# LCD.net
KiCad netlist of a schematic drawn in Altium Designer
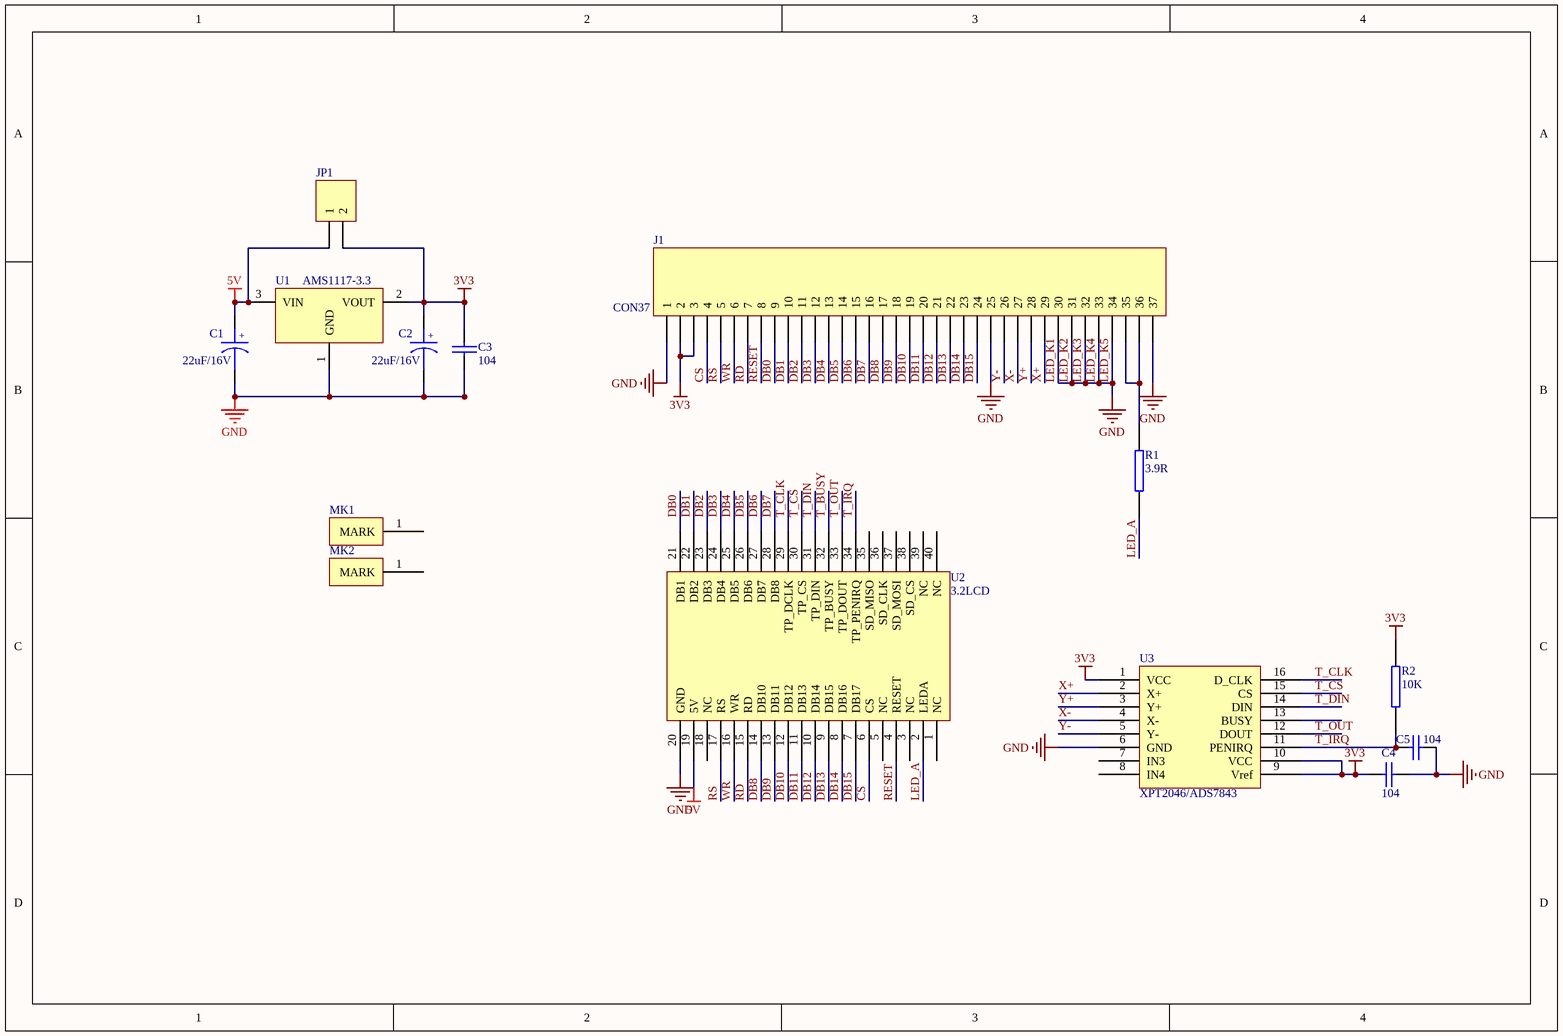
[diagram p0: LCD.SchDoc]

(export (version "E")
  (design (tool "Eeschema 10.0.6"))
  (components
    (comp (ref "C1")
      (value "22uF/16V")
      (footprint "0805C")
      (description "Capacitor")
      (libsource (lib "*") (part "CAPACITOR POL"))
    )
    (comp (ref "C2")
      (value "22uF/16V")
      (footprint "0805C")
      (description "Capacitor")
      (libsource (lib "*") (part "CAPACITOR POL"))
    )
    (comp (ref "C3")
      (value "104")
      (footprint "C0603")
      (description "Capacitor")
      (libsource (lib "*") (part "CAP"))
    )
    (comp (ref "C4")
      (value "104")
      (footprint "C0603")
      (description "Capacitor")
      (libsource (lib "*") (part "CAP"))
    )
    (comp (ref "C5")
      (value "104")
      (footprint "C0603")
      (description "Capacitor")
      (libsource (lib "*") (part "CAP"))
    )
    (comp (ref "J1")
      (value "CON37")
      (footprint "3.2_37PIN_ILI9341B")
      (description "Header, 6-Pin")
      (fields (field (name "PUBLISHER") "Altium Limited"))
      (libsource (lib "mediaV3.0") (part "Header 37"))
    )
    (comp (ref "JP1")
      (value "~")
      (footprint "J")
      (description "Header, 2-Pin")
      (fields (field (name "PUBLISHER") "Altium Limited"))
      (libsource (lib "Miscellaneous Connectors") (part "Header 2"))
    )
    (comp (ref "MK1") (value "~") (footprint "MARK") (libsource (lib "kevin") (part "MARK")))
    (comp (ref "MK2") (value "~") (footprint "MARK") (libsource (lib "kevin") (part "MARK")))
    (comp (ref "R1") (value "3.9R") (footprint "R0603") (libsource (lib "*") (part "RES2")))
    (comp (ref "R2") (value "10K") (footprint "R0603") (libsource (lib "*") (part "RES2")))
    (comp (ref "U1") (value "AMS1117-3.3") (footprint "SOT-223/P2.3") (libsource (lib "*") (part "AMS1117")))
    (comp (ref "U2") (value "3.2LCD") (footprint "LCD-DIP") (libsource (lib "media") (part "3.2LCD")))
    (comp (ref "U3")
      (value "XPT2046/ADS7843")
      (footprint "TSSOP-16")
      (libsource (lib "mediaV3.0") (part "XPT2046"))
    )
  )
  (nets
    (net (code "1") (name "/CS") (class "Default")
      (node (ref "J1") (pin "4") (pinfunction "4_4") (pintype "passive"))
      (node (ref "U2") (pin "6") (pinfunction "CS_6") (pintype "passive"))
    )
    (net (code "2") (name "/DB0") (class "Default")
      (node (ref "J1") (pin "9") (pinfunction "9_9") (pintype "passive"))
      (node (ref "U2") (pin "21") (pinfunction "DB1_21") (pintype "passive"))
    )
    (net (code "3") (name "/DB1") (class "Default")
      (node (ref "J1") (pin "10") (pinfunction "10_10") (pintype "passive"))
      (node (ref "U2") (pin "22") (pinfunction "DB2_22") (pintype "passive"))
    )
    (net (code "4") (name "/DB2") (class "Default")
      (node (ref "J1") (pin "11") (pinfunction "11_11") (pintype "passive"))
      (node (ref "U2") (pin "23") (pinfunction "DB3_23") (pintype "passive"))
    )
    (net (code "5") (name "/DB3") (class "Default")
      (node (ref "J1") (pin "12") (pinfunction "12_12") (pintype "passive"))
      (node (ref "U2") (pin "24") (pinfunction "DB4_24") (pintype "passive"))
    )
    (net (code "6") (name "/DB4") (class "Default")
      (node (ref "J1") (pin "13") (pinfunction "13_13") (pintype "passive"))
      (node (ref "U2") (pin "25") (pinfunction "DB5_25") (pintype "passive"))
    )
    (net (code "7") (name "/DB5") (class "Default")
      (node (ref "J1") (pin "14") (pinfunction "14_14") (pintype "passive"))
      (node (ref "U2") (pin "26") (pinfunction "DB6_26") (pintype "passive"))
    )
    (net (code "8") (name "/DB6") (class "Default")
      (node (ref "J1") (pin "15") (pinfunction "15_15") (pintype "passive"))
      (node (ref "U2") (pin "27") (pinfunction "DB7_27") (pintype "passive"))
    )
    (net (code "9") (name "/DB7") (class "Default")
      (node (ref "J1") (pin "16") (pinfunction "16_16") (pintype "passive"))
      (node (ref "U2") (pin "28") (pinfunction "DB8_28") (pintype "passive"))
    )
    (net (code "10") (name "/DB8") (class "Default")
      (node (ref "J1") (pin "17") (pinfunction "17_17") (pintype "passive"))
      (node (ref "U2") (pin "14") (pinfunction "DB10_14") (pintype "passive"))
    )
    (net (code "11") (name "/DB9") (class "Default")
      (node (ref "J1") (pin "18") (pinfunction "18_18") (pintype "passive"))
      (node (ref "U2") (pin "13") (pinfunction "DB11_13") (pintype "passive"))
    )
    (net (code "12") (name "/DB10") (class "Default")
      (node (ref "J1") (pin "19") (pinfunction "19_19") (pintype "passive"))
      (node (ref "U2") (pin "12") (pinfunction "DB12_12") (pintype "passive"))
    )
    (net (code "13") (name "/DB11") (class "Default")
      (node (ref "J1") (pin "20") (pinfunction "20_20") (pintype "passive"))
      (node (ref "U2") (pin "11") (pinfunction "DB13_11") (pintype "passive"))
    )
    (net (code "14") (name "/DB12") (class "Default")
      (node (ref "J1") (pin "21") (pinfunction "21_21") (pintype "passive"))
      (node (ref "U2") (pin "10") (pinfunction "DB14_10") (pintype "passive"))
    )
    (net (code "15") (name "/DB13") (class "Default")
      (node (ref "J1") (pin "22") (pinfunction "22_22") (pintype "passive"))
      (node (ref "U2") (pin "9") (pinfunction "DB15_9") (pintype "passive"))
    )
    (net (code "16") (name "/DB14") (class "Default")
      (node (ref "J1") (pin "23") (pinfunction "23_23") (pintype "passive"))
      (node (ref "U2") (pin "8") (pinfunction "DB16_8") (pintype "passive"))
    )
    (net (code "17") (name "/DB15") (class "Default")
      (node (ref "J1") (pin "24") (pinfunction "24_24") (pintype "passive"))
      (node (ref "U2") (pin "7") (pinfunction "DB17_7") (pintype "passive"))
    )
    (net (code "18") (name "/LED_A") (class "Default")
      (node (ref "R1") (pin "1") (pinfunction "1_1") (pintype "passive"))
      (node (ref "U2") (pin "2") (pinfunction "LEDA_2") (pintype "passive"))
    )
    (net (code "19") (name "/RD") (class "Default")
      (node (ref "J1") (pin "7") (pinfunction "7_7") (pintype "passive"))
      (node (ref "U2") (pin "15") (pinfunction "RD_15") (pintype "passive"))
    )
    (net (code "20") (name "/RESET") (class "Default")
      (node (ref "J1") (pin "8") (pinfunction "8_8") (pintype "passive"))
      (node (ref "U2") (pin "4") (pinfunction "RESET_4") (pintype "passive"))
    )
    (net (code "21") (name "/RS") (class "Default")
      (node (ref "J1") (pin "5") (pinfunction "5_5") (pintype "passive"))
      (node (ref "U2") (pin "17") (pinfunction "RS_17") (pintype "passive"))
    )
    (net (code "22") (name "/T_BUSY") (class "Default")
      (node (ref "U2") (pin "32") (pinfunction "TP_BUSY_32") (pintype "passive"))
    )
    (net (code "23") (name "/T_CLK") (class "Default")
      (node (ref "U2") (pin "29") (pinfunction "TP_DCLK_29") (pintype "passive"))
      (node (ref "U3") (pin "16") (pinfunction "D_CLK_16") (pintype "passive"))
    )
    (net (code "24") (name "/T_CS") (class "Default")
      (node (ref "U2") (pin "30") (pinfunction "TP_CS_30") (pintype "passive"))
      (node (ref "U3") (pin "15") (pinfunction "CS_15") (pintype "passive"))
    )
    (net (code "25") (name "/T_DIN") (class "Default")
      (node (ref "U2") (pin "31") (pinfunction "TP_DIN_31") (pintype "passive"))
      (node (ref "U3") (pin "14") (pinfunction "DIN_14") (pintype "passive"))
    )
    (net (code "26") (name "/T_IRQ") (class "Default")
      (node (ref "C5") (pin "1") (pinfunction "1_1") (pintype "passive"))
      (node (ref "R2") (pin "2") (pinfunction "2_2") (pintype "passive"))
      (node (ref "U2") (pin "34") (pinfunction "TP_PENIRQ_34") (pintype "passive"))
      (node (ref "U3") (pin "11") (pinfunction "PENIRQ_11") (pintype "passive"))
    )
    (net (code "27") (name "/T_OUT") (class "Default")
      (node (ref "U2") (pin "33") (pinfunction "TP_DOUT_33") (pintype "passive"))
      (node (ref "U3") (pin "12") (pinfunction "DOUT_12") (pintype "passive"))
    )
    (net (code "28") (name "/WR") (class "Default")
      (node (ref "J1") (pin "6") (pinfunction "6_6") (pintype "passive"))
      (node (ref "U2") (pin "16") (pinfunction "WR_16") (pintype "passive"))
    )
    (net (code "29") (name "/X+") (class "Default")
      (node (ref "J1") (pin "29") (pinfunction "29_29") (pintype "passive"))
      (node (ref "U3") (pin "2") (pinfunction "X+_2") (pintype "passive"))
    )
    (net (code "30") (name "/X-") (class "Default")
      (node (ref "J1") (pin "27") (pinfunction "27_27") (pintype "passive"))
      (node (ref "U3") (pin "4") (pinfunction "X-_4") (pintype "passive"))
    )
    (net (code "31") (name "/Y+") (class "Default")
      (node (ref "J1") (pin "28") (pinfunction "28_28") (pintype "passive"))
      (node (ref "U3") (pin "3") (pinfunction "Y+_3") (pintype "passive"))
    )
    (net (code "32") (name "/Y-") (class "Default")
      (node (ref "J1") (pin "26") (pinfunction "26_26") (pintype "passive"))
      (node (ref "U3") (pin "5") (pinfunction "Y-_5") (pintype "passive"))
    )
    (net (code "33") (name "3V3") (class "Default")
      (node (ref "C2") (pin "1") (pinfunction "1_1") (pintype "passive"))
      (node (ref "C3") (pin "1") (pinfunction "1_1") (pintype "passive"))
      (node (ref "C4") (pin "1") (pinfunction "1_1") (pintype "passive"))
      (node (ref "J1") (pin "2") (pinfunction "2_2") (pintype "passive"))
      (node (ref "J1") (pin "3") (pinfunction "3_3") (pintype "passive"))
      (node (ref "JP1") (pin "2") (pinfunction "2_2") (pintype "passive"))
      (node (ref "R2") (pin "1") (pinfunction "1_1") (pintype "passive"))
      (node (ref "U1") (pin "2") (pinfunction "VOUT_2") (pintype "passive"))
      (node (ref "U3") (pin "1") (pinfunction "VCC_1") (pintype "passive"))
      (node (ref "U3") (pin "10") (pinfunction "VCC_10") (pintype "passive"))
      (node (ref "U3") (pin "9") (pinfunction "Vref_9") (pintype "passive"))
    )
    (net (code "34") (name "5V") (class "Default")
      (node (ref "C1") (pin "1") (pinfunction "1_1") (pintype "passive"))
      (node (ref "JP1") (pin "1") (pinfunction "1_1") (pintype "passive"))
      (node (ref "U1") (pin "3") (pinfunction "VIN_3") (pintype "passive"))
      (node (ref "U2") (pin "19") (pinfunction "5V_19") (pintype "passive"))
    )
    (net (code "35") (name "GND") (class "Default")
      (node (ref "C1") (pin "2") (pinfunction "2_2") (pintype "passive"))
      (node (ref "C2") (pin "2") (pinfunction "2_2") (pintype "passive"))
      (node (ref "C3") (pin "2") (pinfunction "2_2") (pintype "passive"))
      (node (ref "C4") (pin "2") (pinfunction "2_2") (pintype "passive"))
      (node (ref "C5") (pin "2") (pinfunction "2_2") (pintype "passive"))
      (node (ref "J1") (pin "1") (pinfunction "1_1") (pintype "passive"))
      (node (ref "J1") (pin "25") (pinfunction "25_25") (pintype "passive"))
      (node (ref "J1") (pin "30") (pinfunction "30_30") (pintype "passive"))
      (node (ref "J1") (pin "31") (pinfunction "31_31") (pintype "passive"))
      (node (ref "J1") (pin "32") (pinfunction "32_32") (pintype "passive"))
      (node (ref "J1") (pin "33") (pinfunction "33_33") (pintype "passive"))
      (node (ref "J1") (pin "34") (pinfunction "34_34") (pintype "passive"))
      (node (ref "J1") (pin "37") (pinfunction "37_37") (pintype "passive"))
      (node (ref "U1") (pin "1") (pinfunction "GND_1") (pintype "passive"))
      (node (ref "U2") (pin "20") (pinfunction "GND_20") (pintype "passive"))
      (node (ref "U3") (pin "6") (pinfunction "GND_6") (pintype "passive"))
    )
    (net (code "36") (name "Net-(J1-Pad35)") (class "Default")
      (node (ref "J1") (pin "35") (pinfunction "35_35") (pintype "passive"))
      (node (ref "J1") (pin "36") (pinfunction "36_36") (pintype "passive"))
      (node (ref "R1") (pin "2") (pinfunction "2_2") (pintype "passive"))
    )
    (net (code "37") (name "unconnected-(MK1-MARK-Pad1)") (class "Default")
      (node (ref "MK1") (pin "1") (pinfunction "MARK_1") (pintype "passive"))
    )
    (net (code "38") (name "unconnected-(MK2-MARK-Pad1)") (class "Default")
      (node (ref "MK2") (pin "1") (pinfunction "MARK_1") (pintype "passive"))
    )
    (net (code "39") (name "unconnected-(U2-NC-Pad1)") (class "Default")
      (node (ref "U2") (pin "1") (pinfunction "NC_1") (pintype "passive"))
    )
    (net (code "40") (name "unconnected-(U2-NC-Pad3)") (class "Default")
      (node (ref "U2") (pin "3") (pinfunction "NC_3") (pintype "passive"))
    )
    (net (code "41") (name "unconnected-(U2-NC-Pad5)") (class "Default")
      (node (ref "U2") (pin "5") (pinfunction "NC_5") (pintype "passive"))
    )
    (net (code "42") (name "unconnected-(U2-NC-Pad18)") (class "Default")
      (node (ref "U2") (pin "18") (pinfunction "NC_18") (pintype "passive"))
    )
    (net (code "43") (name "unconnected-(U2-NC-Pad39)") (class "Default")
      (node (ref "U2") (pin "39") (pinfunction "NC_39") (pintype "passive"))
    )
    (net (code "44") (name "unconnected-(U2-NC-Pad40)") (class "Default")
      (node (ref "U2") (pin "40") (pinfunction "NC_40") (pintype "passive"))
    )
    (net (code "45") (name "unconnected-(U2-SD_CLK-Pad36)") (class "Default")
      (node (ref "U2") (pin "36") (pinfunction "SD_CLK_36") (pintype "passive"))
    )
    (net (code "46") (name "unconnected-(U2-SD_CS-Pad38)") (class "Default")
      (node (ref "U2") (pin "38") (pinfunction "SD_CS_38") (pintype "passive"))
    )
    (net (code "47") (name "unconnected-(U2-SD_MISO-Pad35)") (class "Default")
      (node (ref "U2") (pin "35") (pinfunction "SD_MISO_35") (pintype "passive"))
    )
    (net (code "48") (name "unconnected-(U2-SD_MOSI-Pad37)") (class "Default")
      (node (ref "U2") (pin "37") (pinfunction "SD_MOSI_37") (pintype "passive"))
    )
    (net (code "49") (name "unconnected-(U3-BUSY-Pad13)") (class "Default")
      (node (ref "U3") (pin "13") (pinfunction "BUSY_13") (pintype "passive"))
    )
    (net (code "50") (name "unconnected-(U3-IN3-Pad7)") (class "Default")
      (node (ref "U3") (pin "7") (pinfunction "IN3_7") (pintype "passive"))
    )
    (net (code "51") (name "unconnected-(U3-IN4-Pad8)") (class "Default")
      (node (ref "U3") (pin "8") (pinfunction "IN4_8") (pintype "passive"))
    )
  )
)
